# SIPM_ASSY_CON.net
KiCad netlist of a schematic drawn in Altium Designer
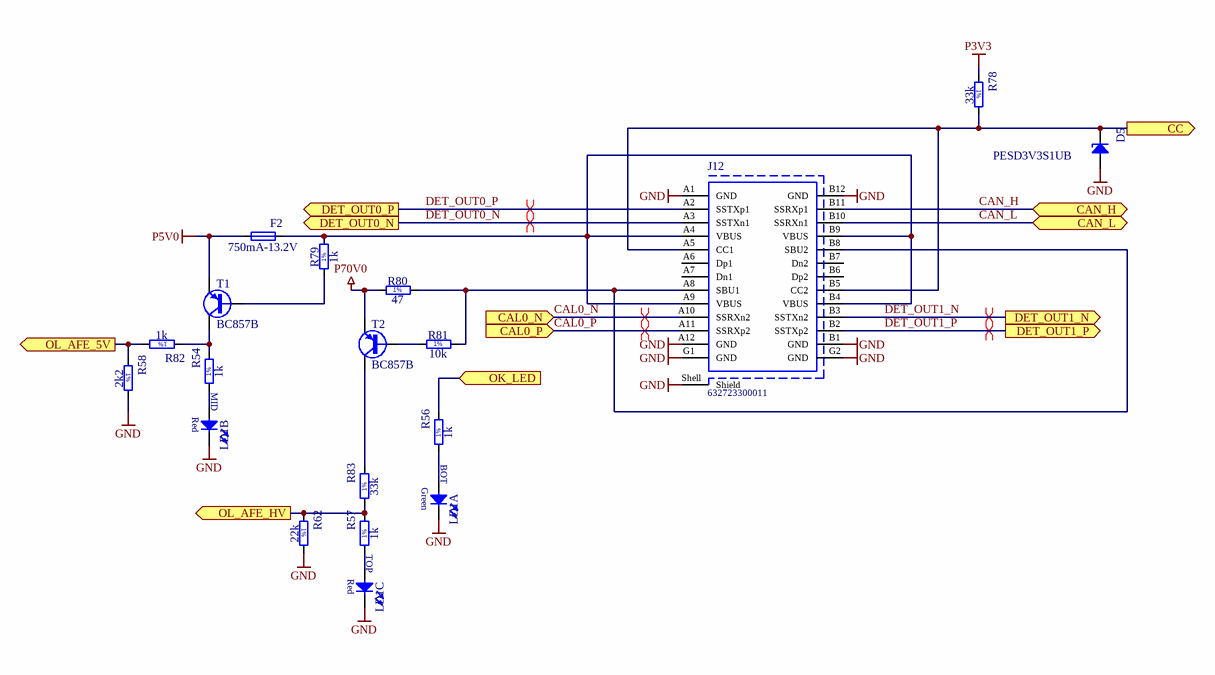
[diagram p0: SIPM_ASSY_CON.SchDoc]

(export (version "E")
  (design (tool "Eeschema 10.0.6"))
  (components
    (comp (ref "D5")
      (value "PESD3V3S1UB")
      (footprint "SODFL1608X65N")
      (description "ESD protection diode")
      (fields
        (field (name "VOLTAGE") "3V3")
        (field (name "POWER") "330W")
        (field (name "AUTHOR") "CERN DEM JLC")
      )
      (libsource (lib "ICs And Semiconductors") (part "Diode ESD"))
    )
    (comp (ref "F2")
      (value "750mA-13.2V")
      (footprint "FUSRC4632X90N")
      (description "Fuse")
      (fields
        (field (name "PART NUMBER") "FUSR1812_LITTELFUSE_MINISMDC075F-2")
        (field (name "MANUFACTURER") "LITTELFUSE")
        (field (name "AUTHOR") "CERN DEM JLC")
      )
      (libsource (lib "Eletro-mechanical") (part "Fuse"))
    )
    (comp (ref "J12")
      (value "632723300011")
      (footprint "632723300011")
      (description "USB 3.1 Type C Receptacle WR-COM, Horizontal, SMT / THT")
      (fields (field (name "PUBLISHER") "Wurth Elektronik"))
      (libsource (lib "ALTIUM-WR-COM_USB_31-rev18d") (part "632723300011"))
    )
    (comp (ref "LD1")
      (value "Red/Red/Green")
      (footprint "LED_DIALIGHT_570-0100-112F")
      (description "LED x3  Top Red, Middle Red, Bottom Green")
      (fields
        (field (name "PART NUMBER") "LED_DIALIGHT_570-0100-112F")
        (field (name "MANUFACTURER") "DIALIGHT")
        (field (name "AUTHOR") "CERN DEM JLC")
      )
      (libsource (lib "ICs And Semiconductors") (part "LED x3 G-1C2A-BOT_R-3C4A_R-5C6A-TOP"))
    )
    (comp (ref "R54")
      (value "1k")
      (footprint "RESC1005X40N")
      (description "Resistor - 1%")
      (fields
        (field (name "PART NUMBER") "R0402_1K_1%_0.0625W_100PPM")
        (field (name "POWER") "0.0625W")
        (field (name "AUTHOR") "CERN DEM JLC")
      )
      (libsource (lib "Resistors") (part "Resistor - 1%"))
    )
    (comp (ref "R56")
      (value "1k")
      (footprint "RESC1005X40N")
      (description "Resistor - 1%")
      (fields
        (field (name "PART NUMBER") "R0402_1K_1%_0.0625W_100PPM")
        (field (name "POWER") "0.0625W")
        (field (name "AUTHOR") "CERN DEM JLC")
      )
      (libsource (lib "Resistors") (part "Resistor - 1%"))
    )
    (comp (ref "R57")
      (value "1k")
      (footprint "RESC1005X40N")
      (description "Resistor - 1%")
      (fields
        (field (name "PART NUMBER") "R0402_1K_1%_0.0625W_100PPM")
        (field (name "POWER") "0.0625W")
        (field (name "AUTHOR") "CERN DEM JLC")
      )
      (libsource (lib "Resistors") (part "Resistor - 1%"))
    )
    (comp (ref "R58")
      (value "2k2")
      (footprint "RESC1005X40N")
      (description "Resistor - 1%")
      (fields
        (field (name "PART NUMBER") "R0402_2K2_1%_0.0625W_100PPM")
        (field (name "POWER") "0.0625W")
        (field (name "AUTHOR") "CERN DEM JLC")
      )
      (libsource (lib "Resistors") (part "Resistor - 1%"))
    )
    (comp (ref "R62")
      (value "22k")
      (footprint "RESC1005X40N")
      (description "Resistor - 1%")
      (fields
        (field (name "PART NUMBER") "R0402_22K_1%_0.0625W_100PPM")
        (field (name "POWER") "0.0625W")
        (field (name "AUTHOR") "CERN DEM JLC")
      )
      (libsource (lib "Resistors") (part "Resistor - 1%"))
    )
    (comp (ref "R78")
      (value "33k")
      (footprint "RESC2012X60N")
      (description "Resistor - 1%")
      (fields
        (field (name "PART NUMBER") "R0805_33K_1%_0.125W_100PPM")
        (field (name "POWER") "0.125W")
        (field (name "AUTHOR") "CERN DEM JLC")
      )
      (libsource (lib "Resistors") (part "Resistor - 1%"))
    )
    (comp (ref "R79")
      (value "1k")
      (footprint "RESC1005X40N")
      (description "Resistor - 1%")
      (fields
        (field (name "PART NUMBER") "R0402_1K_1%_0.0625W_100PPM")
        (field (name "POWER") "0.0625W")
        (field (name "AUTHOR") "CERN DEM JLC")
      )
      (libsource (lib "Resistors") (part "Resistor - 1%"))
    )
    (comp (ref "R80")
      (value "47")
      (footprint "RESC1608X55N")
      (description "Resistor - 1%")
      (fields
        (field (name "PART NUMBER") "R0603_47R_1%_0.1W_100PPM")
        (field (name "POWER") "0.1W")
        (field (name "AUTHOR") "CERN DEM JLC")
      )
      (libsource (lib "Resistors") (part "Resistor - 1%"))
    )
    (comp (ref "R81")
      (value "10k")
      (footprint "RESC2012X60N")
      (description "Resistor - 1%")
      (fields
        (field (name "PART NUMBER") "R0805_10K_1%_0.125W_100PPM")
        (field (name "POWER") "0.125W")
        (field (name "AUTHOR") "CERN DEM JLC")
      )
      (libsource (lib "Resistors") (part "Resistor - 1%"))
    )
    (comp (ref "R82")
      (value "1k")
      (footprint "RESC1005X40N")
      (description "Resistor - 1%")
      (fields
        (field (name "PART NUMBER") "R0402_1K_1%_0.0625W_100PPM")
        (field (name "POWER") "0.0625W")
        (field (name "AUTHOR") "CERN DEM JLC")
      )
      (libsource (lib "Resistors") (part "Resistor - 1%"))
    )
    (comp (ref "R83")
      (value "33k")
      (footprint "RESC2012X60N")
      (description "Resistor - 1%")
      (fields
        (field (name "PART NUMBER") "R0805_33K_1%_0.125W_100PPM")
        (field (name "POWER") "0.125W")
        (field (name "AUTHOR") "CERN DEM JLC")
      )
      (libsource (lib "Resistors") (part "Resistor - 1%"))
    )
    (comp (ref "T1")
      (value "BC857B")
      (footprint "SOT95P230X110-3N")
      (description "PNP Transistor")
      (fields (field (name "MANUFACTURER") "NXP SEMICONDUCTORS") (field (name "AUTHOR") "CERN DEM JLC"))
      (libsource (lib "ICs And Semiconductors") (part "PNP B1 E2 C3"))
    )
    (comp (ref "T2")
      (value "BC857B")
      (footprint "SOT95P230X110-3N")
      (description "PNP Transistor")
      (fields (field (name "MANUFACTURER") "NXP SEMICONDUCTORS") (field (name "AUTHOR") "CERN DEM JLC"))
      (libsource (lib "ICs And Semiconductors") (part "PNP B1 E2 C3"))
    )
  )
  (nets
    (net (code "1") (name "/CAL0_N") (class "Default")
      (node (ref "J12") (pin "A10") (pinfunction "SSRXn2_A10") (pintype "passive"))
    )
    (net (code "2") (name "/CAL0_P") (class "Default")
      (node (ref "J12") (pin "A11") (pinfunction "SSRXp2_A11") (pintype "passive"))
    )
    (net (code "3") (name "/CAN_H") (class "Default")
      (node (ref "J12") (pin "B11") (pinfunction "SSRXp1_B11") (pintype "passive"))
    )
    (net (code "4") (name "/CAN_L") (class "Default")
      (node (ref "J12") (pin "B10") (pinfunction "SSRXn1_B10") (pintype "passive"))
    )
    (net (code "5") (name "/CC") (class "Default")
      (node (ref "D5") (pin "1") (pinfunction "C_1") (pintype "passive"))
      (node (ref "J12") (pin "A5") (pinfunction "CC1_A5") (pintype "passive"))
      (node (ref "J12") (pin "B5") (pinfunction "CC2_B5") (pintype "passive"))
      (node (ref "R78") (pin "2") (pinfunction "2_2") (pintype "passive"))
    )
    (net (code "6") (name "/DET_OUT0_N") (class "Default")
      (node (ref "J12") (pin "A3") (pinfunction "SSTXn1_A3") (pintype "passive"))
    )
    (net (code "7") (name "/DET_OUT0_P") (class "Default")
      (node (ref "J12") (pin "A2") (pinfunction "SSTXp1_A2") (pintype "passive"))
    )
    (net (code "8") (name "/DET_OUT1_N") (class "Default")
      (node (ref "J12") (pin "B3") (pinfunction "SSTXn2_B3") (pintype "passive"))
    )
    (net (code "9") (name "/DET_OUT1_P") (class "Default")
      (node (ref "J12") (pin "B2") (pinfunction "SSTXp2_B2") (pintype "passive"))
    )
    (net (code "10") (name "/OK_LED") (class "Default")
      (node (ref "R56") (pin "2") (pinfunction "2_2") (pintype "passive"))
    )
    (net (code "11") (name "/OL_AFE_5V") (class "Default")
      (node (ref "R58") (pin "1") (pinfunction "1_1") (pintype "passive"))
      (node (ref "R82") (pin "2") (pinfunction "2_2") (pintype "passive"))
    )
    (net (code "12") (name "/OL_AFE_HV") (class "Default")
      (node (ref "R57") (pin "2") (pinfunction "2_2") (pintype "passive"))
      (node (ref "R62") (pin "1") (pinfunction "1_1") (pintype "passive"))
      (node (ref "R83") (pin "1") (pinfunction "1_1") (pintype "passive"))
    )
    (net (code "13") (name "GND") (class "Default")
      (node (ref "D5") (pin "2") (pinfunction "A_2") (pintype "passive"))
      (node (ref "J12") (pin "A1") (pinfunction "GND_A1") (pintype "passive"))
      (node (ref "J12") (pin "A12") (pinfunction "GND_A12") (pintype "passive"))
      (node (ref "J12") (pin "B1") (pinfunction "GND_B1") (pintype "passive"))
      (node (ref "J12") (pin "B12") (pinfunction "GND_B12") (pintype "passive"))
      (node (ref "J12") (pin "G1") (pinfunction "GND_G1") (pintype "passive"))
      (node (ref "J12") (pin "G2") (pinfunction "GND_G2") (pintype "passive"))
      (node (ref "J12") (pin "Shell") (pinfunction "Shield_Shell") (pintype "passive"))
      (node (ref "LD1") (pin "2") (pinfunction "C_2") (pintype "passive"))
      (node (ref "LD1") (pin "4") (pinfunction "C_4") (pintype "passive"))
      (node (ref "LD1") (pin "6") (pinfunction "C_6") (pintype "passive"))
      (node (ref "R58") (pin "2") (pinfunction "2_2") (pintype "passive"))
      (node (ref "R62") (pin "2") (pinfunction "2_2") (pintype "passive"))
    )
    (net (code "14") (name "Net-(F2-Pad2)") (class "Default")
      (node (ref "F2") (pin "2") (pinfunction "2_2") (pintype "passive"))
      (node (ref "J12") (pin "A4") (pinfunction "VBUS_A4") (pintype "passive"))
      (node (ref "J12") (pin "A9") (pinfunction "VBUS_A9") (pintype "passive"))
      (node (ref "J12") (pin "B4") (pinfunction "VBUS_B4") (pintype "passive"))
      (node (ref "J12") (pin "B9") (pinfunction "VBUS_B9") (pintype "passive"))
      (node (ref "R79") (pin "2") (pinfunction "2_2") (pintype "passive"))
    )
    (net (code "15") (name "Net-(J12-SBU1)") (class "Default")
      (node (ref "J12") (pin "A8") (pinfunction "SBU1_A8") (pintype "passive"))
      (node (ref "J12") (pin "B8") (pinfunction "SBU2_B8") (pintype "passive"))
      (node (ref "R80") (pin "2") (pinfunction "2_2") (pintype "passive"))
      (node (ref "R81") (pin "2") (pinfunction "2_2") (pintype "passive"))
    )
    (net (code "16") (name "Net-(LD1A-A)") (class "Default")
      (node (ref "LD1") (pin "1") (pinfunction "A_1") (pintype "passive"))
      (node (ref "R56") (pin "1") (pinfunction "1_1") (pintype "passive"))
    )
    (net (code "17") (name "Net-(LD1B-A)") (class "Default")
      (node (ref "LD1") (pin "3") (pinfunction "A_3") (pintype "passive"))
      (node (ref "R54") (pin "1") (pinfunction "1_1") (pintype "passive"))
    )
    (net (code "18") (name "Net-(LD1C-A)") (class "Default")
      (node (ref "LD1") (pin "5") (pinfunction "A_5") (pintype "passive"))
      (node (ref "R57") (pin "1") (pinfunction "1_1") (pintype "passive"))
    )
    (net (code "19") (name "Net-(T1-B)") (class "Default")
      (node (ref "R79") (pin "1") (pinfunction "1_1") (pintype "passive"))
      (node (ref "T1") (pin "1") (pinfunction "B_1") (pintype "passive"))
    )
    (net (code "20") (name "Net-(T1-C)") (class "Default")
      (node (ref "R54") (pin "2") (pinfunction "2_2") (pintype "passive"))
      (node (ref "R82") (pin "1") (pinfunction "1_1") (pintype "passive"))
      (node (ref "T1") (pin "3") (pinfunction "C_3") (pintype "passive"))
    )
    (net (code "21") (name "Net-(T2-B)") (class "Default")
      (node (ref "R81") (pin "1") (pinfunction "1_1") (pintype "passive"))
      (node (ref "T2") (pin "1") (pinfunction "B_1") (pintype "passive"))
    )
    (net (code "22") (name "Net-(T2-C)") (class "Default")
      (node (ref "R83") (pin "2") (pinfunction "2_2") (pintype "passive"))
      (node (ref "T2") (pin "3") (pinfunction "C_3") (pintype "passive"))
    )
    (net (code "23") (name "P3V3") (class "Default")
      (node (ref "R78") (pin "1") (pinfunction "1_1") (pintype "passive"))
    )
    (net (code "24") (name "P5V0") (class "Default")
      (node (ref "F2") (pin "1") (pinfunction "1_1") (pintype "passive"))
      (node (ref "T1") (pin "2") (pinfunction "E_2") (pintype "passive"))
    )
    (net (code "25") (name "P70V0") (class "Default")
      (node (ref "R80") (pin "1") (pinfunction "1_1") (pintype "passive"))
      (node (ref "T2") (pin "2") (pinfunction "E_2") (pintype "passive"))
    )
    (net (code "26") (name "unconnected-(J12-Dn1-PadA7)") (class "Default")
      (node (ref "J12") (pin "A7") (pinfunction "Dn1_A7") (pintype "passive"))
    )
    (net (code "27") (name "unconnected-(J12-Dn2-PadB7)") (class "Default")
      (node (ref "J12") (pin "B7") (pinfunction "Dn2_B7") (pintype "passive"))
    )
    (net (code "28") (name "unconnected-(J12-Dp1-PadA6)") (class "Default")
      (node (ref "J12") (pin "A6") (pinfunction "Dp1_A6") (pintype "passive"))
    )
    (net (code "29") (name "unconnected-(J12-Dp2-PadB6)") (class "Default")
      (node (ref "J12") (pin "B6") (pinfunction "Dp2_B6") (pintype "passive"))
    )
  )
)
